# Adafruit_CAN_Bus_FeatherWing.net
KiCad netlist of a schematic drawn in EAGLE
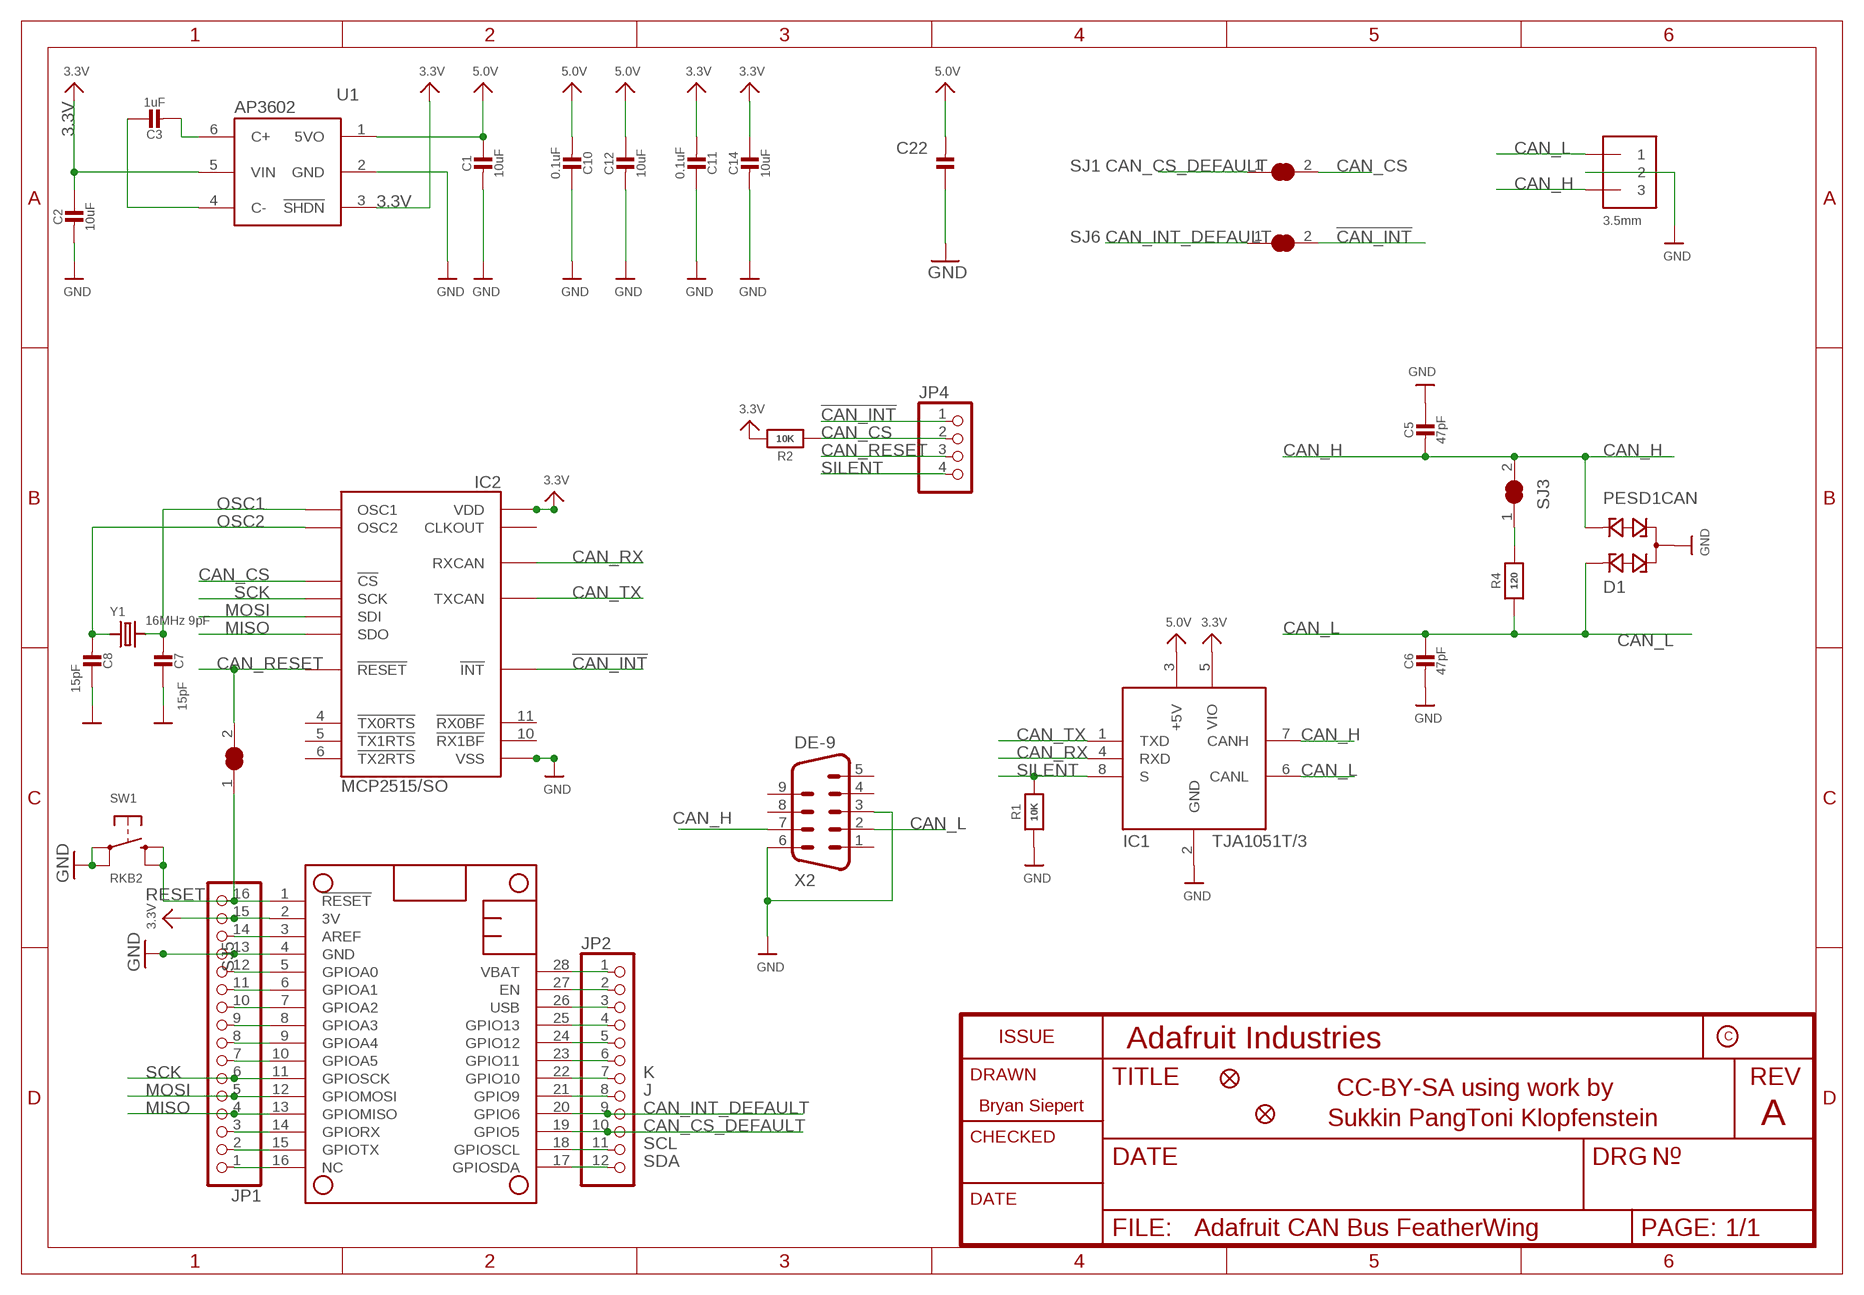
[diagram p0: schematic, sheet 1]

(export (version "E")
  (design (tool "Eeschema 10.0.6"))
  (components
    (comp (ref "C1")
      (value "10uF")
      (footprint "eagle-import:0805-NO")
      (libsource (lib "eagle-import") (part "CAP_CERAMIC0805-NOOUTLINE"))
    )
    (comp (ref "C2")
      (value "10uF")
      (footprint "eagle-import:0805-NO")
      (libsource (lib "eagle-import") (part "CAP_CERAMIC0805-NOOUTLINE"))
    )
    (comp (ref "C3")
      (value "1uF")
      (footprint "eagle-import:0805-NO")
      (libsource (lib "eagle-import") (part "CAP_CERAMIC0805-NOOUTLINE"))
    )
    (comp (ref "C5")
      (value "47pF")
      (footprint "eagle-import:0603-NO")
      (libsource (lib "eagle-import") (part "CAP_CERAMIC0603_NO"))
    )
    (comp (ref "C6")
      (value "47pF")
      (footprint "eagle-import:0603-NO")
      (libsource (lib "eagle-import") (part "CAP_CERAMIC0603_NO"))
    )
    (comp (ref "C7")
      (value "15pF")
      (footprint "eagle-import:0603-NO")
      (libsource (lib "eagle-import") (part "CAP_CERAMIC0603_NO"))
    )
    (comp (ref "C8")
      (value "15pF")
      (footprint "eagle-import:0603-NO")
      (libsource (lib "eagle-import") (part "CAP_CERAMIC0603_NO"))
    )
    (comp (ref "C10")
      (value "0.1uF")
      (footprint "eagle-import:0603-NO")
      (libsource (lib "eagle-import") (part "CAP_CERAMIC0603_NO"))
    )
    (comp (ref "C11")
      (value "0.1uF")
      (footprint "eagle-import:0603-NO")
      (libsource (lib "eagle-import") (part "CAP_CERAMIC0603_NO"))
    )
    (comp (ref "C12")
      (value "10uF")
      (footprint "eagle-import:0805-NO")
      (libsource (lib "eagle-import") (part "CAP_CERAMIC0805-NOOUTLINE"))
    )
    (comp (ref "C14")
      (value "10uF")
      (footprint "eagle-import:0805-NO")
      (libsource (lib "eagle-import") (part "CAP_CERAMIC0805-NOOUTLINE"))
    )
    (comp (ref "C22")
      (value "0.1uF")
      (footprint "eagle-import:0603-NO")
      (libsource (lib "eagle-import") (part "CAP_CERAMIC0603_NO"))
    )
    (comp (ref "D1")
      (value "PESD1CAN")
      (footprint "eagle-import:SOT23")
      (libsource (lib "eagle-import") (part "PESD1CAN"))
    )
    (comp (ref "FID2")
      (value "FIDUCIAL_1MM")
      (footprint "eagle-import:FIDUCIAL_1MM")
      (libsource (lib "eagle-import") (part "FIDUCIAL_1MM"))
    )
    (comp (ref "FID3")
      (value "FIDUCIAL_1MM")
      (footprint "eagle-import:FIDUCIAL_1MM")
      (libsource (lib "eagle-import") (part "FIDUCIAL_1MM"))
    )
    (comp (ref "IC1")
      (value "TJA1051T/3")
      (footprint "eagle-import:SOIC8_150MIL")
      (libsource (lib "eagle-import") (part "CAN_TRANSCIEVER_TCAN1051V"))
    )
    (comp (ref "IC2")
      (value "MCP2515/SO")
      (footprint "eagle-import:SOIC18WIDE")
      (libsource (lib "eagle-import") (part "MCP2515/SO"))
    )
    (comp (ref "JP1")
      (value "HEADER-1X16ROUND")
      (footprint "eagle-import:1X16_ROUND")
      (libsource (lib "eagle-import") (part "HEADER-1X16ROUND"))
    )
    (comp (ref "JP2")
      (value "HEADER-1X12")
      (footprint "eagle-import:1X12_ROUND")
      (libsource (lib "eagle-import") (part "HEADER-1X12"))
    )
    (comp (ref "JP4")
      (value "HEADER-1X4ROUND")
      (footprint "eagle-import:1X04_ROUND")
      (libsource (lib "eagle-import") (part "HEADER-1X4ROUND"))
    )
    (comp (ref "MS1")
      (value "FEATHERWING_NODIM")
      (footprint "eagle-import:FEATHERWING_NODIM")
      (libsource (lib "eagle-import") (part "FEATHERWING_NODIM"))
    )
    (comp (ref "NEOPIX1")
      (value "3.5mm")
      (footprint "eagle-import:TERMBLOCK_1X3-3.5MM")
      (libsource (lib "eagle-import") (part "TERMBLOCK_1X3"))
    )
    (comp (ref "R1")
      (value "10K")
      (footprint "eagle-import:0603-NO")
      (libsource (lib "eagle-import") (part "RESISTOR_0603_NOOUT"))
    )
    (comp (ref "R2")
      (value "10K")
      (footprint "eagle-import:0603-NO")
      (libsource (lib "eagle-import") (part "RESISTOR_0603_NOOUT"))
    )
    (comp (ref "R4")
      (value "120")
      (footprint "eagle-import:0603-NO")
      (libsource (lib "eagle-import") (part "RESISTOR_0603_NOOUT"))
    )
    (comp (ref "SJ1")
      (value "SOLDERJUMPER_CLOSED")
      (footprint "eagle-import:SOLDERJUMPER_CLOSEDWIRE")
      (libsource (lib "eagle-import") (part "SOLDERJUMPER_CLOSED"))
    )
    (comp (ref "SJ3")
      (value "SOLDERJUMPER_CLOSED")
      (footprint "eagle-import:SOLDERJUMPER_CLOSEDWIRE")
      (libsource (lib "eagle-import") (part "SOLDERJUMPER_CLOSED"))
    )
    (comp (ref "SJ5")
      (value "SOLDERJUMPER_CLOSED")
      (footprint "eagle-import:SOLDERJUMPER_CLOSEDWIRE")
      (libsource (lib "eagle-import") (part "SOLDERJUMPER_CLOSED"))
    )
    (comp (ref "SJ6")
      (value "SOLDERJUMPER_CLOSED")
      (footprint "eagle-import:SOLDERJUMPER_CLOSEDWIRE")
      (libsource (lib "eagle-import") (part "SOLDERJUMPER_CLOSED"))
    )
    (comp (ref "SW1")
      (value "RKB2")
      (footprint "eagle-import:BTN_RKB2_4.6X2.8")
      (libsource (lib "eagle-import") (part "SWITCH_TACT_SMT_RKB2"))
    )
    (comp (ref "U1")
      (value "AP3602")
      (footprint "eagle-import:SOT23-6")
      (libsource (lib "eagle-import") (part "AP3602"))
    )
    (comp (ref "X2")
      (value "DE-9")
      (footprint "eagle-import:M09D")
      (libsource (lib "eagle-import") (part "M09D"))
    )
    (comp (ref "Y1")
      (value "16MHz 9pF")
      (footprint "eagle-import:CRYSTAL_3.2X2.5")
      (libsource (lib "eagle-import") (part "CRYSTAL3.2X2.5"))
    )
  )
  (nets
    (net (code "1") (name "/CAN_CS") (class "Default")
      (node (ref "IC2") (pin "16") (pinfunction "~{CS}_16") (pintype "input"))
      (node (ref "JP4") (pin "2") (pinfunction "2_2") (pintype "passive"))
      (node (ref "R2") (pin "1") (pinfunction "1_1") (pintype "passive"))
      (node (ref "SJ1") (pin "2") (pinfunction "2_2") (pintype "passive"))
    )
    (net (code "2") (name "/CAN_CS_DEFAULT") (class "Default")
      (node (ref "JP2") (pin "10") (pinfunction "10_10") (pintype "passive"))
      (node (ref "MS1") (pin "19") (pinfunction "GPIO5_19") (pintype "bidirectional"))
      (node (ref "SJ1") (pin "1") (pinfunction "1_1") (pintype "passive"))
    )
    (net (code "3") (name "/CAN_H") (class "Default")
      (node (ref "C5") (pin "2") (pinfunction "2_2") (pintype "passive"))
      (node (ref "D1") (pin "2") (pinfunction "2_2") (pintype "passive"))
      (node (ref "IC1") (pin "7") (pinfunction "CANH_7") (pintype "bidirectional"))
      (node (ref "NEOPIX1") (pin "3") (pinfunction "3_3") (pintype "passive"))
      (node (ref "SJ3") (pin "2") (pinfunction "2_2") (pintype "passive"))
      (node (ref "X2") (pin "7") (pinfunction "7_7") (pintype "passive"))
    )
    (net (code "4") (name "/CAN_INT_DEFAULT") (class "Default")
      (node (ref "JP2") (pin "9") (pinfunction "9_9") (pintype "passive"))
      (node (ref "MS1") (pin "20") (pinfunction "GPIO6_20") (pintype "bidirectional"))
      (node (ref "SJ6") (pin "1") (pinfunction "1_1") (pintype "passive"))
    )
    (net (code "5") (name "/CAN_L") (class "Default")
      (node (ref "C6") (pin "1") (pinfunction "1_1") (pintype "passive"))
      (node (ref "D1") (pin "1") (pinfunction "1_1") (pintype "passive"))
      (node (ref "IC1") (pin "6") (pinfunction "CANL_6") (pintype "bidirectional"))
      (node (ref "NEOPIX1") (pin "1") (pinfunction "1_1") (pintype "passive"))
      (node (ref "R4") (pin "1") (pinfunction "1_1") (pintype "passive"))
      (node (ref "X2") (pin "2") (pinfunction "2_2") (pintype "passive"))
    )
    (net (code "6") (name "/CAN_RESET") (class "Default")
      (node (ref "IC2") (pin "17") (pinfunction "~{RESET}_17") (pintype "input"))
      (node (ref "JP4") (pin "3") (pinfunction "3_3") (pintype "passive"))
      (node (ref "SJ5") (pin "2") (pinfunction "2_2") (pintype "passive"))
    )
    (net (code "7") (name "/CAN_RX") (class "Default")
      (node (ref "IC1") (pin "4") (pinfunction "RXD_4") (pintype "output"))
      (node (ref "IC2") (pin "2") (pinfunction "RXCAN_2") (pintype "bidirectional"))
    )
    (net (code "8") (name "/CAN_TX") (class "Default")
      (node (ref "IC1") (pin "1") (pinfunction "TXD_1") (pintype "input"))
      (node (ref "IC2") (pin "1") (pinfunction "TXCAN_1") (pintype "bidirectional"))
    )
    (net (code "9") (name "/J") (class "Default")
      (node (ref "JP2") (pin "8") (pinfunction "8_8") (pintype "passive"))
      (node (ref "MS1") (pin "21") (pinfunction "GPIO9_21") (pintype "bidirectional"))
    )
    (net (code "10") (name "/K") (class "Default")
      (node (ref "JP2") (pin "7") (pinfunction "7_7") (pintype "passive"))
      (node (ref "MS1") (pin "22") (pinfunction "GPIO10_22") (pintype "bidirectional"))
    )
    (net (code "11") (name "/MISO") (class "Default")
      (node (ref "IC2") (pin "15") (pinfunction "SDO_15") (pintype "output"))
      (node (ref "JP1") (pin "4") (pinfunction "4_4") (pintype "passive"))
      (node (ref "MS1") (pin "13") (pinfunction "GPIOMISO_13") (pintype "bidirectional"))
    )
    (net (code "12") (name "/MOSI") (class "Default")
      (node (ref "IC2") (pin "14") (pinfunction "SDI_14") (pintype "input"))
      (node (ref "JP1") (pin "5") (pinfunction "5_5") (pintype "passive"))
      (node (ref "MS1") (pin "12") (pinfunction "GPIOMOSI_12") (pintype "bidirectional"))
    )
    (net (code "13") (name "/OSC1") (class "Default")
      (node (ref "C7") (pin "2") (pinfunction "2_2") (pintype "passive"))
      (node (ref "IC2") (pin "8") (pinfunction "OSC1_8") (pintype "bidirectional"))
      (node (ref "Y1") (pin "2") (pinfunction "2_2") (pintype "passive"))
    )
    (net (code "14") (name "/OSC2") (class "Default")
      (node (ref "C8") (pin "2") (pinfunction "2_2") (pintype "passive"))
      (node (ref "IC2") (pin "7") (pinfunction "OSC2_7") (pintype "bidirectional"))
      (node (ref "Y1") (pin "1") (pinfunction "1_1") (pintype "passive"))
    )
    (net (code "15") (name "/RESET") (class "Default")
      (node (ref "JP1") (pin "16") (pinfunction "16_16") (pintype "passive"))
      (node (ref "MS1") (pin "1") (pinfunction "~{RESET}_1") (pintype "input"))
      (node (ref "SJ5") (pin "1") (pinfunction "1_1") (pintype "passive"))
      (node (ref "SW1") (pin "B") (pinfunction "S_B") (pintype "passive"))
      (node (ref "SW1") (pin "B'") (pinfunction "S1_B'") (pintype "passive"))
    )
    (net (code "16") (name "/SCK") (class "Default")
      (node (ref "IC2") (pin "13") (pinfunction "SCK_13") (pintype "input"))
      (node (ref "JP1") (pin "6") (pinfunction "6_6") (pintype "passive"))
      (node (ref "MS1") (pin "11") (pinfunction "GPIOSCK_11") (pintype "bidirectional"))
    )
    (net (code "17") (name "/SCL") (class "Default")
      (node (ref "JP2") (pin "11") (pinfunction "11_11") (pintype "passive"))
      (node (ref "MS1") (pin "18") (pinfunction "GPIOSCL_18") (pintype "bidirectional"))
    )
    (net (code "18") (name "/SDA") (class "Default")
      (node (ref "JP2") (pin "12") (pinfunction "12_12") (pintype "passive"))
      (node (ref "MS1") (pin "17") (pinfunction "GPIOSDA_17") (pintype "bidirectional"))
    )
    (net (code "19") (name "/SILENT") (class "Default")
      (node (ref "IC1") (pin "8") (pinfunction "S_8") (pintype "input"))
      (node (ref "JP4") (pin "4") (pinfunction "4_4") (pintype "passive"))
      (node (ref "R1") (pin "2") (pinfunction "2_2") (pintype "passive"))
    )
    (net (code "20") (name "/~{CAN_INT}") (class "Default")
      (node (ref "IC2") (pin "12") (pinfunction "~{INT}_12") (pintype "bidirectional"))
      (node (ref "JP4") (pin "1") (pinfunction "1_1") (pintype "passive"))
      (node (ref "SJ6") (pin "2") (pinfunction "2_2") (pintype "passive"))
    )
    (net (code "21") (name "3.3V") (class "Default")
      (node (ref "C11") (pin "2") (pinfunction "2_2") (pintype "passive"))
      (node (ref "C14") (pin "1") (pinfunction "1_1") (pintype "passive"))
      (node (ref "C2") (pin "1") (pinfunction "1_1") (pintype "passive"))
      (node (ref "IC1") (pin "5") (pinfunction "VIO_5") (pintype "power_in"))
      (node (ref "IC2") (pin "18") (pinfunction "VDD_18") (pintype "power_in"))
      (node (ref "JP1") (pin "15") (pinfunction "15_15") (pintype "passive"))
      (node (ref "MS1") (pin "2") (pinfunction "3V_2") (pintype "power_in"))
      (node (ref "R2") (pin "2") (pinfunction "2_2") (pintype "passive"))
      (node (ref "U1") (pin "3") (pinfunction "~{SHDN}_3") (pintype "input"))
      (node (ref "U1") (pin "5") (pinfunction "VIN_5") (pintype "power_in"))
    )
    (net (code "22") (name "5.0V") (class "Default")
      (node (ref "C1") (pin "1") (pinfunction "1_1") (pintype "passive"))
      (node (ref "C10") (pin "2") (pinfunction "2_2") (pintype "passive"))
      (node (ref "C12") (pin "1") (pinfunction "1_1") (pintype "passive"))
      (node (ref "C22") (pin "2") (pinfunction "2_2") (pintype "passive"))
      (node (ref "IC1") (pin "3") (pinfunction "+5V_3") (pintype "power_in"))
      (node (ref "U1") (pin "1") (pinfunction "5VO_1") (pintype "power_in"))
    )
    (net (code "23") (name "GND") (class "Default")
      (node (ref "C1") (pin "2") (pinfunction "2_2") (pintype "passive"))
      (node (ref "C10") (pin "1") (pinfunction "1_1") (pintype "passive"))
      (node (ref "C11") (pin "1") (pinfunction "1_1") (pintype "passive"))
      (node (ref "C12") (pin "2") (pinfunction "2_2") (pintype "passive"))
      (node (ref "C14") (pin "2") (pinfunction "2_2") (pintype "passive"))
      (node (ref "C2") (pin "2") (pinfunction "2_2") (pintype "passive"))
      (node (ref "C22") (pin "1") (pinfunction "1_1") (pintype "passive"))
      (node (ref "C5") (pin "1") (pinfunction "1_1") (pintype "passive"))
      (node (ref "C6") (pin "2") (pinfunction "2_2") (pintype "passive"))
      (node (ref "C7") (pin "1") (pinfunction "1_1") (pintype "passive"))
      (node (ref "C8") (pin "1") (pinfunction "1_1") (pintype "passive"))
      (node (ref "D1") (pin "3") (pinfunction "3_3") (pintype "passive"))
      (node (ref "IC1") (pin "2") (pinfunction "GND_2") (pintype "power_in"))
      (node (ref "IC2") (pin "9") (pinfunction "VSS_9") (pintype "power_in"))
      (node (ref "JP1") (pin "13") (pinfunction "13_13") (pintype "passive"))
      (node (ref "MS1") (pin "4") (pinfunction "GND_4") (pintype "power_in"))
      (node (ref "NEOPIX1") (pin "2") (pinfunction "2_2") (pintype "passive"))
      (node (ref "R1") (pin "1") (pinfunction "1_1") (pintype "passive"))
      (node (ref "SW1") (pin "A") (pinfunction "P_A") (pintype "passive"))
      (node (ref "SW1") (pin "A'") (pinfunction "P1_A'") (pintype "passive"))
      (node (ref "U1") (pin "2") (pinfunction "GND_2") (pintype "power_in"))
      (node (ref "X2") (pin "3") (pinfunction "3_3") (pintype "passive"))
      (node (ref "X2") (pin "6") (pinfunction "6_6") (pintype "passive"))
    )
    (net (code "24") (name "Net-(MS1-AREF)") (class "Default")
      (node (ref "JP1") (pin "14") (pinfunction "14_14") (pintype "passive"))
      (node (ref "MS1") (pin "3") (pinfunction "AREF_3") (pintype "passive"))
    )
    (net (code "25") (name "Net-(MS1-EN)") (class "Default")
      (node (ref "JP2") (pin "2") (pinfunction "2_2") (pintype "passive"))
      (node (ref "MS1") (pin "27") (pinfunction "EN_27") (pintype "passive"))
    )
    (net (code "26") (name "Net-(MS1-GPIO11)") (class "Default")
      (node (ref "JP2") (pin "6") (pinfunction "6_6") (pintype "passive"))
      (node (ref "MS1") (pin "23") (pinfunction "GPIO11_23") (pintype "bidirectional"))
    )
    (net (code "27") (name "Net-(MS1-GPIO12)") (class "Default")
      (node (ref "JP2") (pin "5") (pinfunction "5_5") (pintype "passive"))
      (node (ref "MS1") (pin "24") (pinfunction "GPIO12_24") (pintype "bidirectional"))
    )
    (net (code "28") (name "Net-(MS1-GPIO13)") (class "Default")
      (node (ref "JP2") (pin "4") (pinfunction "4_4") (pintype "passive"))
      (node (ref "MS1") (pin "25") (pinfunction "GPIO13_25") (pintype "bidirectional"))
    )
    (net (code "29") (name "Net-(MS1-GPIOA0)") (class "Default")
      (node (ref "JP1") (pin "12") (pinfunction "12_12") (pintype "passive"))
      (node (ref "MS1") (pin "5") (pinfunction "GPIOA0_5") (pintype "bidirectional"))
    )
    (net (code "30") (name "Net-(MS1-GPIOA1)") (class "Default")
      (node (ref "JP1") (pin "11") (pinfunction "11_11") (pintype "passive"))
      (node (ref "MS1") (pin "6") (pinfunction "GPIOA1_6") (pintype "bidirectional"))
    )
    (net (code "31") (name "Net-(MS1-GPIOA2)") (class "Default")
      (node (ref "JP1") (pin "10") (pinfunction "10_10") (pintype "passive"))
      (node (ref "MS1") (pin "7") (pinfunction "GPIOA2_7") (pintype "bidirectional"))
    )
    (net (code "32") (name "Net-(MS1-GPIOA3)") (class "Default")
      (node (ref "JP1") (pin "9") (pinfunction "9_9") (pintype "passive"))
      (node (ref "MS1") (pin "8") (pinfunction "GPIOA3_8") (pintype "bidirectional"))
    )
    (net (code "33") (name "Net-(MS1-GPIOA4)") (class "Default")
      (node (ref "JP1") (pin "8") (pinfunction "8_8") (pintype "passive"))
      (node (ref "MS1") (pin "9") (pinfunction "GPIOA4_9") (pintype "bidirectional"))
    )
    (net (code "34") (name "Net-(MS1-GPIOA5)") (class "Default")
      (node (ref "JP1") (pin "7") (pinfunction "7_7") (pintype "passive"))
      (node (ref "MS1") (pin "10") (pinfunction "GPIOA5_10") (pintype "bidirectional"))
    )
    (net (code "35") (name "Net-(MS1-GPIORX)") (class "Default")
      (node (ref "JP1") (pin "3") (pinfunction "3_3") (pintype "passive"))
      (node (ref "MS1") (pin "14") (pinfunction "GPIORX_14") (pintype "bidirectional"))
    )
    (net (code "36") (name "Net-(MS1-GPIOTX)") (class "Default")
      (node (ref "JP1") (pin "2") (pinfunction "2_2") (pintype "passive"))
      (node (ref "MS1") (pin "15") (pinfunction "GPIOTX_15") (pintype "bidirectional"))
    )
    (net (code "37") (name "Net-(MS1-NC)") (class "Default")
      (node (ref "JP1") (pin "1") (pinfunction "1_1") (pintype "passive"))
      (node (ref "MS1") (pin "16") (pinfunction "NC_16") (pintype "passive"))
    )
    (net (code "38") (name "Net-(MS1-USB)") (class "Default")
      (node (ref "JP2") (pin "3") (pinfunction "3_3") (pintype "passive"))
      (node (ref "MS1") (pin "26") (pinfunction "USB_26") (pintype "power_in"))
    )
    (net (code "39") (name "Net-(MS1-VBAT)") (class "Default")
      (node (ref "JP2") (pin "1") (pinfunction "1_1") (pintype "passive"))
      (node (ref "MS1") (pin "28") (pinfunction "VBAT_28") (pintype "power_in"))
    )
    (net (code "40") (name "Net-(R4-Pad2)") (class "Default")
      (node (ref "R4") (pin "2") (pinfunction "2_2") (pintype "passive"))
      (node (ref "SJ3") (pin "1") (pinfunction "1_1") (pintype "passive"))
    )
    (net (code "41") (name "Net-(U1-C+)") (class "Default")
      (node (ref "C3") (pin "2") (pinfunction "2_2") (pintype "passive"))
      (node (ref "U1") (pin "6") (pinfunction "C+_6") (pintype "bidirectional"))
    )
    (net (code "42") (name "Net-(U1-C-)") (class "Default")
      (node (ref "C3") (pin "1") (pinfunction "1_1") (pintype "passive"))
      (node (ref "U1") (pin "4") (pinfunction "C-_4") (pintype "bidirectional"))
    )
    (net (code "43") (name "unconnected-(IC2-CLKOUT-Pad3)") (class "Default")
      (node (ref "IC2") (pin "3") (pinfunction "CLKOUT_3") (pintype "output"))
    )
    (net (code "44") (name "unconnected-(IC2-~{RX0BF}-Pad11)") (class "Default")
      (node (ref "IC2") (pin "11") (pinfunction "~{RX0BF}_11") (pintype "bidirectional"))
    )
    (net (code "45") (name "unconnected-(IC2-~{RX1BF}-Pad10)") (class "Default")
      (node (ref "IC2") (pin "10") (pinfunction "~{RX1BF}_10") (pintype "bidirectional"))
    )
    (net (code "46") (name "unconnected-(IC2-~{TX0RTS}-Pad4)") (class "Default")
      (node (ref "IC2") (pin "4") (pinfunction "~{TX0RTS}_4") (pintype "bidirectional"))
    )
    (net (code "47") (name "unconnected-(IC2-~{TX1RTS}-Pad5)") (class "Default")
      (node (ref "IC2") (pin "5") (pinfunction "~{TX1RTS}_5") (pintype "bidirectional"))
    )
    (net (code "48") (name "unconnected-(IC2-~{TX2RTS}-Pad6)") (class "Default")
      (node (ref "IC2") (pin "6") (pinfunction "~{TX2RTS}_6") (pintype "bidirectional"))
    )
    (net (code "49") (name "unconnected-(X2-Pad1)") (class "Default")
      (node (ref "X2") (pin "1") (pinfunction "1_1") (pintype "passive"))
    )
    (net (code "50") (name "unconnected-(X2-Pad4)") (class "Default")
      (node (ref "X2") (pin "4") (pinfunction "4_4") (pintype "passive"))
    )
    (net (code "51") (name "unconnected-(X2-Pad5)") (class "Default")
      (node (ref "X2") (pin "5") (pinfunction "5_5") (pintype "passive"))
    )
    (net (code "52") (name "unconnected-(X2-Pad8)") (class "Default")
      (node (ref "X2") (pin "8") (pinfunction "8_8") (pintype "passive"))
    )
    (net (code "53") (name "unconnected-(X2-Pad9)") (class "Default")
      (node (ref "X2") (pin "9") (pinfunction "9_9") (pintype "passive"))
    )
  )
)
